# keychain_rev2.net
KiCad netlist of a schematic drawn in EAGLE
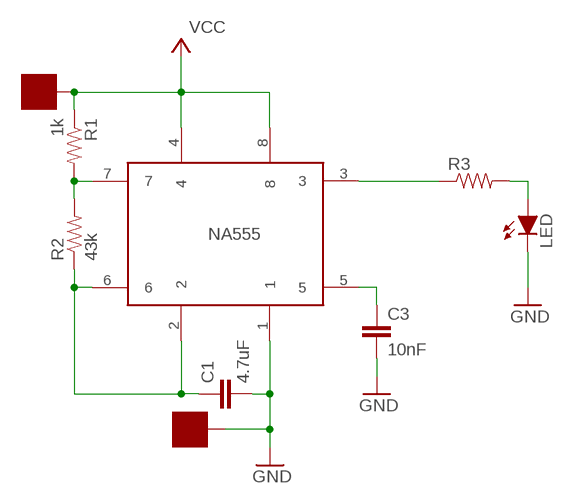
[diagram p0: schematic, sheet 1]

(export (version "E")
  (design (tool "Eeschema 10.0.6"))
  (components
    (comp (ref "5V")
      (value "SOLDER_PAD")
      (footprint "eagle-import:SOLDER_PAD_XSMALL")
      (libsource (lib "eagle-import") (part "SOLDER_PAD"))
    )
    (comp (ref "C1")
      (value "4.7uF")
      (footprint "eagle-import:0603-CAP")
      (fields (field (name "TOLERANCE") "5%") (field (name "VOLTAGE") "25V"))
      (libsource (lib "eagle-import") (part "CAP0603-CAP"))
    )
    (comp (ref "C3")
      (value "10nF")
      (footprint "eagle-import:0603-CAP")
      (fields (field (name "TOLERANCE") "5%") (field (name "VOLTAGE") "25V"))
      (libsource (lib "eagle-import") (part "CAP0603-CAP"))
    )
    (comp (ref "GND")
      (value "SOLDER_PAD")
      (footprint "eagle-import:SOLDER_PAD_XSMALL")
      (libsource (lib "eagle-import") (part "SOLDER_PAD"))
    )
    (comp (ref "LED")
      (value "LED-0603")
      (footprint "eagle-import:LED-603")
      (libsource (lib "eagle-import") (part "LED-0603"))
    )
    (comp (ref "NA555")
      (value "NA555SO-8")
      (footprint "eagle-import:SOIC-08")
      (libsource (lib "eagle-import") (part "NA555SO-8"))
    )
    (comp (ref "R1")
      (value "1k")
      (footprint "eagle-import:0603-RES")
      (fields (field (name "TOLERANCE") "1%"))
      (libsource (lib "eagle-import") (part "RESISTOR0603-RES"))
    )
    (comp (ref "R2")
      (value "43k")
      (footprint "eagle-import:0603-RES")
      (fields (field (name "TOLERANCE") "1%"))
      (libsource (lib "eagle-import") (part "RESISTOR0603-RES"))
    )
    (comp (ref "R3")
      (value "RESISTOR0603")
      (footprint "eagle-import:0603-RES")
      (libsource (lib "eagle-import") (part "RESISTOR0603"))
    )
  )
  (nets
    (net (code "1") (name "GND") (class "Default")
      (node (ref "C1") (pin "2") (pinfunction "2_2") (pintype "passive"))
      (node (ref "C3") (pin "2") (pinfunction "2_2") (pintype "passive"))
      (node (ref "GND") (pin "P$1") (pinfunction "P$1_P$1") (pintype "bidirectional"))
      (node (ref "LED") (pin "C") (pinfunction "C_C") (pintype "passive"))
      (node (ref "NA555") (pin "1") (pinfunction "1_1") (pintype "bidirectional"))
    )
    (net (code "2") (name "Net-(C1-Pad1)") (class "Default")
      (node (ref "C1") (pin "1") (pinfunction "1_1") (pintype "passive"))
      (node (ref "NA555") (pin "2") (pinfunction "2_2") (pintype "bidirectional"))
      (node (ref "NA555") (pin "6") (pinfunction "6_6") (pintype "bidirectional"))
      (node (ref "R2") (pin "1") (pinfunction "1_1") (pintype "passive"))
    )
    (net (code "3") (name "Net-(C3-Pad1)") (class "Default")
      (node (ref "C3") (pin "1") (pinfunction "1_1") (pintype "passive"))
      (node (ref "NA555") (pin "5") (pinfunction "5_5") (pintype "bidirectional"))
    )
    (net (code "4") (name "Net-(LED-PadA)") (class "Default")
      (node (ref "LED") (pin "A") (pinfunction "A_A") (pintype "passive"))
      (node (ref "R3") (pin "2") (pinfunction "2_2") (pintype "passive"))
    )
    (net (code "5") (name "Net-(NA555-Pad3)") (class "Default")
      (node (ref "NA555") (pin "3") (pinfunction "3_3") (pintype "bidirectional"))
      (node (ref "R3") (pin "1") (pinfunction "1_1") (pintype "passive"))
    )
    (net (code "6") (name "Net-(NA555-Pad7)") (class "Default")
      (node (ref "NA555") (pin "7") (pinfunction "7_7") (pintype "bidirectional"))
      (node (ref "R1") (pin "2") (pinfunction "2_2") (pintype "passive"))
      (node (ref "R2") (pin "2") (pinfunction "2_2") (pintype "passive"))
    )
    (net (code "7") (name "VCC") (class "Default")
      (node (ref "5V") (pin "P$1") (pinfunction "P$1_P$1") (pintype "bidirectional"))
      (node (ref "NA555") (pin "4") (pinfunction "4_4") (pintype "bidirectional"))
      (node (ref "NA555") (pin "8") (pinfunction "8_8") (pintype "bidirectional"))
      (node (ref "R1") (pin "1") (pinfunction "1_1") (pintype "passive"))
    )
  )
)
